# ASD2612.net
KiCad netlist of a schematic drawn in EAGLE
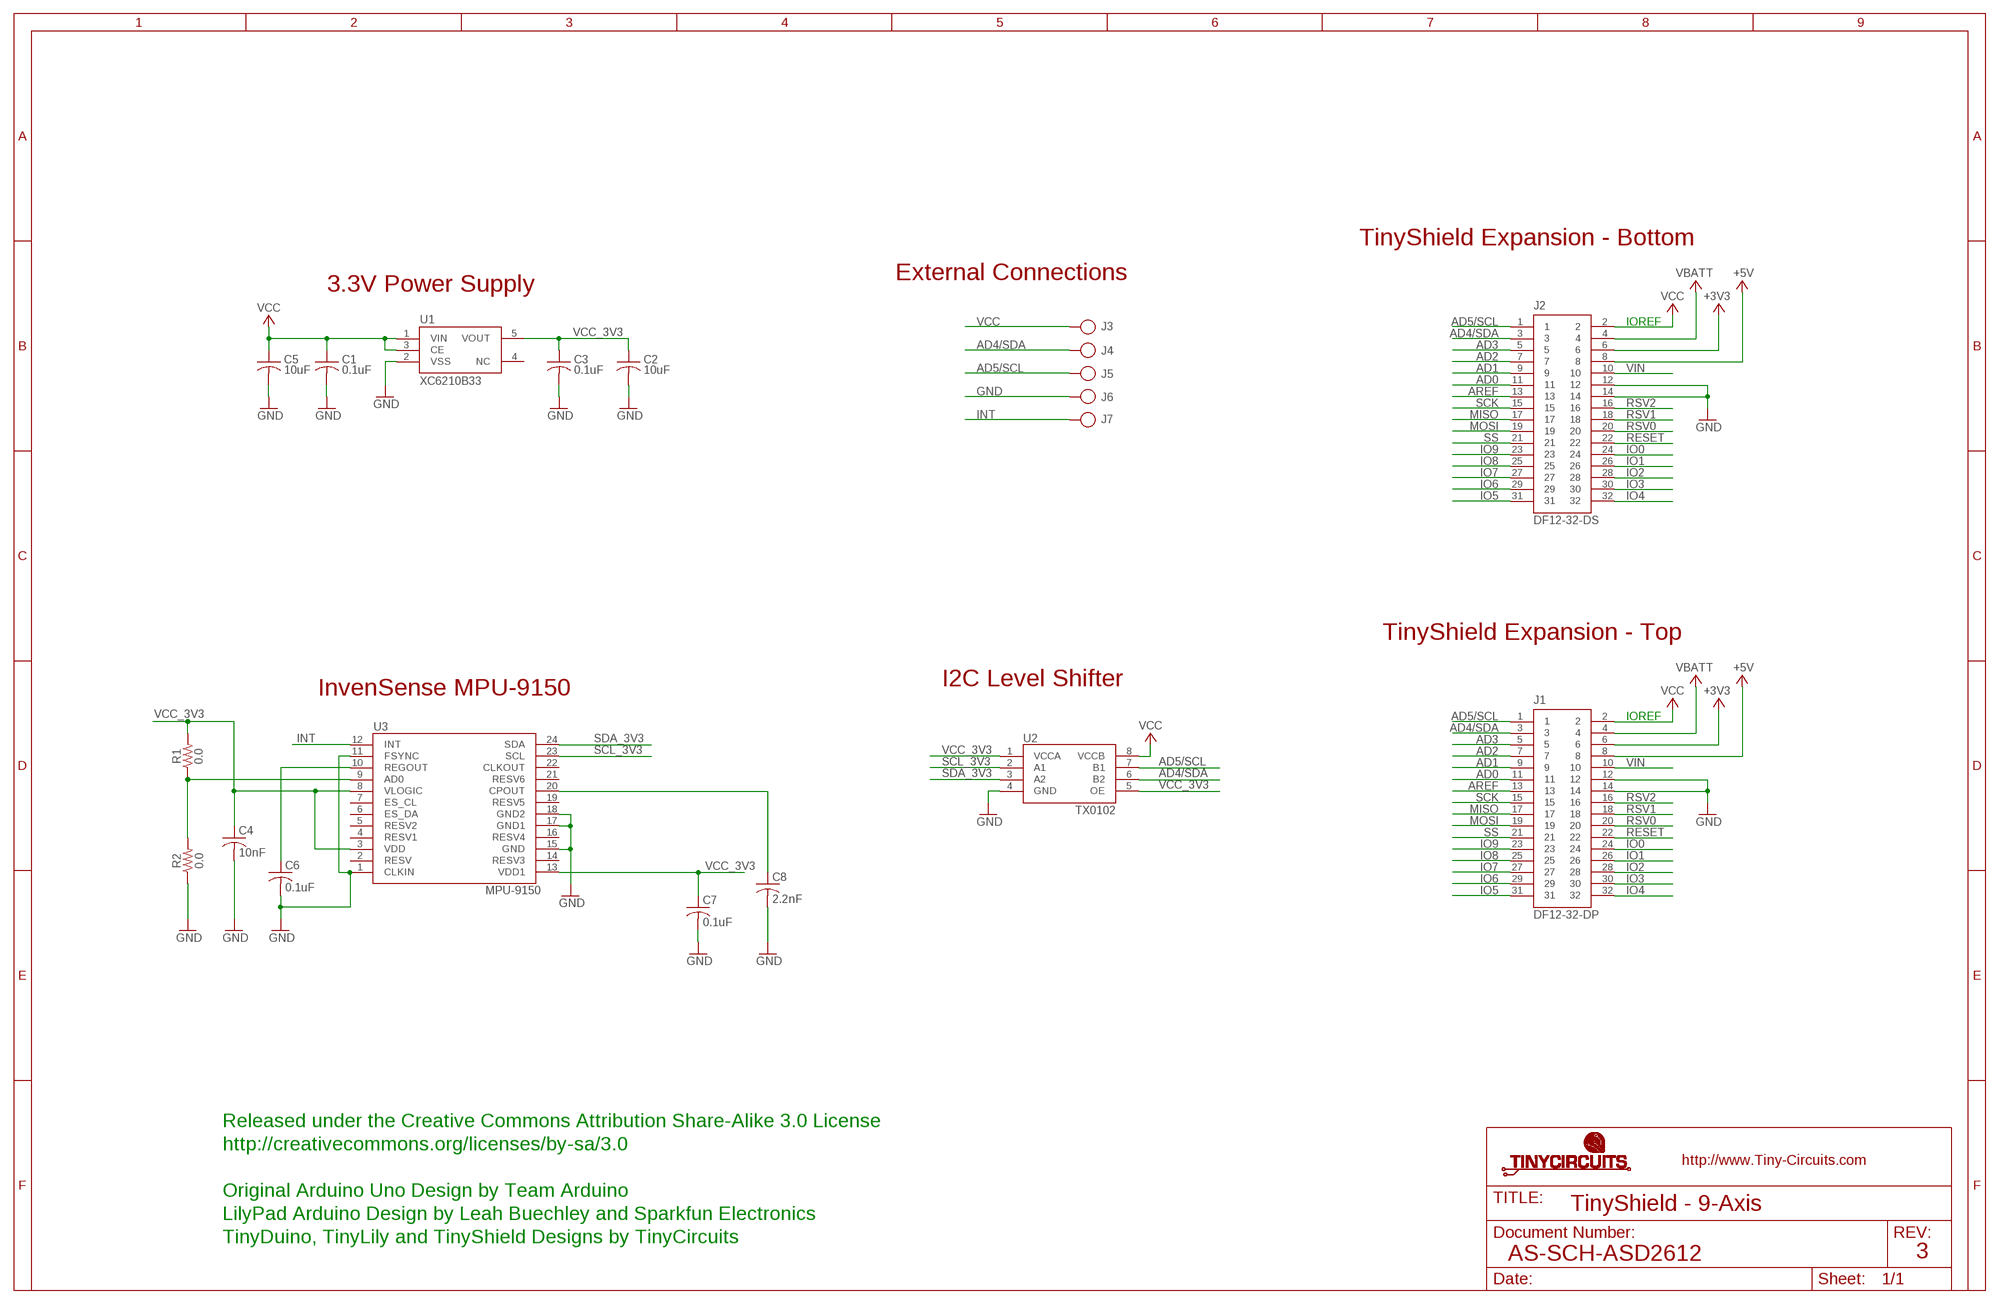
[diagram p0: schematic, sheet 1]

(export (version "E")
  (design (tool "Eeschema 10.0.6"))
  (components
    (comp (ref "C1")
      (value "0.1uF")
      (footprint "eagle-import:C0402")
      (fields (field (name "PARTNO") "AS-ITM-00008") (field (name "PARTNO_1") "AS-ITM-00008"))
      (libsource (lib "eagle-import") (part "AS-ITM-00008"))
    )
    (comp (ref "C2")
      (value "10uF")
      (footprint "eagle-import:C0805")
      (fields (field (name "PARTNO") "AS-ITM-00045") (field (name "PARTNO_1") "AS-ITM-00045"))
      (libsource (lib "eagle-import") (part "AS-ITM-00045"))
    )
    (comp (ref "C3")
      (value "0.1uF")
      (footprint "eagle-import:C0402")
      (fields (field (name "PARTNO") "AS-ITM-00008") (field (name "PARTNO_1") "AS-ITM-00008"))
      (libsource (lib "eagle-import") (part "AS-ITM-00008"))
    )
    (comp (ref "C4")
      (value "10nF")
      (footprint "eagle-import:C0402")
      (fields (field (name "PARTNO") "AS-ITM-00084"))
      (libsource (lib "eagle-import") (part "AS-ITM-00084"))
    )
    (comp (ref "C5")
      (value "10uF")
      (footprint "eagle-import:C0805")
      (fields (field (name "PARTNO") "AS-ITM-00045"))
      (libsource (lib "eagle-import") (part "AS-ITM-00045"))
    )
    (comp (ref "C6")
      (value "0.1uF")
      (footprint "eagle-import:C0402")
      (fields (field (name "PARTNO") "AS-ITM-00008"))
      (libsource (lib "eagle-import") (part "AS-ITM-00008"))
    )
    (comp (ref "C7")
      (value "0.1uF")
      (footprint "eagle-import:C0402")
      (fields (field (name "PARTNO") "AS-ITM-00008"))
      (libsource (lib "eagle-import") (part "AS-ITM-00008"))
    )
    (comp (ref "C8")
      (value "2.2nF")
      (footprint "eagle-import:C0402")
      (fields (field (name "PARTNO") "AS-ITM-00085"))
      (libsource (lib "eagle-import") (part "AS-ITM-00085"))
    )
    (comp (ref "J1")
      (value "DF12-32-DP")
      (footprint "eagle-import:DF12-32-DP")
      (fields (field (name "PARTNO") "AS-ITM-00015") (field (name "PARTNO_1") "AS-ITM-00015"))
      (libsource (lib "eagle-import") (part "AS-ITM-00015"))
    )
    (comp (ref "J2")
      (value "DF12-32-DS")
      (footprint "eagle-import:DF12-32-DS")
      (fields (field (name "PARTNO") "AS-ITM-00012") (field (name "PARTNO_1") "AS-ITM-00012"))
      (libsource (lib "eagle-import") (part "AS-ITM-00012"))
    )
    (comp (ref "J3")
      (value "PIN_1X.1\"")
      (footprint "eagle-import:1X.1_")
      (libsource (lib "eagle-import") (part "PIN_1X.1{dblquote}"))
    )
    (comp (ref "J4")
      (value "PIN_1X.1\"")
      (footprint "eagle-import:1X.1_")
      (libsource (lib "eagle-import") (part "PIN_1X.1{dblquote}"))
    )
    (comp (ref "J5")
      (value "PIN_1X.1\"")
      (footprint "eagle-import:1X.1_")
      (libsource (lib "eagle-import") (part "PIN_1X.1{dblquote}"))
    )
    (comp (ref "J6")
      (value "PIN_1X.1\"")
      (footprint "eagle-import:1X.1_")
      (libsource (lib "eagle-import") (part "PIN_1X.1{dblquote}"))
    )
    (comp (ref "J7")
      (value "PIN_1X.1\"")
      (footprint "eagle-import:1X.1_")
      (libsource (lib "eagle-import") (part "PIN_1X.1{dblquote}"))
    )
    (comp (ref "R1")
      (value "0.0")
      (footprint "eagle-import:0402")
      (fields (field (name "PARTNO") "AS-ITM-00076"))
      (libsource (lib "eagle-import") (part "AS-ITM-00076"))
    )
    (comp (ref "R2")
      (value "AS-ITM-000760402_SHORT")
      (footprint "eagle-import:0402_SHORT")
      (libsource (lib "eagle-import") (part "AS-ITM-000760402_SHORT"))
    )
    (comp (ref "U1")
      (value "XC6210B33")
      (footprint "eagle-import:SOT-25")
      (fields (field (name "PARTNO") "AS-ITM-00046"))
      (libsource (lib "eagle-import") (part "AS-ITM-00046"))
    )
    (comp (ref "U2")
      (value "TX0102")
      (footprint "eagle-import:DQE(R-PX2SON-N8)")
      (fields (field (name "PARTNO") "AS-ITM-00073"))
      (libsource (lib "eagle-import") (part "AS-ITM-00073"))
    )
    (comp (ref "U3")
      (value "MPU-9150")
      (footprint "eagle-import:MPU-9150")
      (fields (field (name "PARTNO") "AS-ITM-00081"))
      (libsource (lib "eagle-import") (part "AS-ITM-00081"))
    )
  )
  (nets
    (net (code "1") (name "+3V3") (class "Default")
      (node (ref "J1") (pin "6") (pinfunction "6_6") (pintype "bidirectional"))
      (node (ref "J2") (pin "6") (pinfunction "6_6") (pintype "bidirectional"))
    )
    (net (code "2") (name "+5V") (class "Default")
      (node (ref "J1") (pin "8") (pinfunction "8_8") (pintype "bidirectional"))
      (node (ref "J2") (pin "8") (pinfunction "8_8") (pintype "bidirectional"))
    )
    (net (code "3") (name "/AD0") (class "Default")
      (node (ref "J1") (pin "11") (pinfunction "11_11") (pintype "bidirectional"))
      (node (ref "J2") (pin "11") (pinfunction "11_11") (pintype "bidirectional"))
    )
    (net (code "4") (name "/AD1") (class "Default")
      (node (ref "J1") (pin "9") (pinfunction "9_9") (pintype "bidirectional"))
      (node (ref "J2") (pin "9") (pinfunction "9_9") (pintype "bidirectional"))
    )
    (net (code "5") (name "/AD2") (class "Default")
      (node (ref "J1") (pin "7") (pinfunction "7_7") (pintype "bidirectional"))
      (node (ref "J2") (pin "7") (pinfunction "7_7") (pintype "bidirectional"))
    )
    (net (code "6") (name "/AD3") (class "Default")
      (node (ref "J1") (pin "5") (pinfunction "5_5") (pintype "bidirectional"))
      (node (ref "J2") (pin "5") (pinfunction "5_5") (pintype "bidirectional"))
    )
    (net (code "7") (name "/AD4{slash}SDA") (class "Default")
      (node (ref "J1") (pin "3") (pinfunction "3_3") (pintype "bidirectional"))
      (node (ref "J2") (pin "3") (pinfunction "3_3") (pintype "bidirectional"))
      (node (ref "J4") (pin "1") (pinfunction "1_1") (pintype "bidirectional"))
      (node (ref "U2") (pin "6") (pinfunction "B2_6") (pintype "bidirectional"))
    )
    (net (code "8") (name "/AD5{slash}SCL") (class "Default")
      (node (ref "J1") (pin "1") (pinfunction "1_1") (pintype "bidirectional"))
      (node (ref "J2") (pin "1") (pinfunction "1_1") (pintype "bidirectional"))
      (node (ref "J5") (pin "1") (pinfunction "1_1") (pintype "bidirectional"))
      (node (ref "U2") (pin "7") (pinfunction "B1_7") (pintype "bidirectional"))
    )
    (net (code "9") (name "/AREF") (class "Default")
      (node (ref "J1") (pin "13") (pinfunction "13_13") (pintype "bidirectional"))
      (node (ref "J2") (pin "13") (pinfunction "13_13") (pintype "bidirectional"))
    )
    (net (code "10") (name "/INT") (class "Default")
      (node (ref "J7") (pin "1") (pinfunction "1_1") (pintype "bidirectional"))
      (node (ref "U3") (pin "12") (pinfunction "INT_12") (pintype "bidirectional"))
    )
    (net (code "11") (name "/IO0") (class "Default")
      (node (ref "J1") (pin "24") (pinfunction "24_24") (pintype "bidirectional"))
      (node (ref "J2") (pin "24") (pinfunction "24_24") (pintype "bidirectional"))
    )
    (net (code "12") (name "/IO1") (class "Default")
      (node (ref "J1") (pin "26") (pinfunction "26_26") (pintype "bidirectional"))
      (node (ref "J2") (pin "26") (pinfunction "26_26") (pintype "bidirectional"))
    )
    (net (code "13") (name "/IO2") (class "Default")
      (node (ref "J1") (pin "28") (pinfunction "28_28") (pintype "bidirectional"))
      (node (ref "J2") (pin "28") (pinfunction "28_28") (pintype "bidirectional"))
    )
    (net (code "14") (name "/IO3") (class "Default")
      (node (ref "J1") (pin "30") (pinfunction "30_30") (pintype "bidirectional"))
      (node (ref "J2") (pin "30") (pinfunction "30_30") (pintype "bidirectional"))
    )
    (net (code "15") (name "/IO4") (class "Default")
      (node (ref "J1") (pin "32") (pinfunction "32_32") (pintype "bidirectional"))
      (node (ref "J2") (pin "32") (pinfunction "32_32") (pintype "bidirectional"))
    )
    (net (code "16") (name "/IO5") (class "Default")
      (node (ref "J1") (pin "31") (pinfunction "31_31") (pintype "bidirectional"))
      (node (ref "J2") (pin "31") (pinfunction "31_31") (pintype "bidirectional"))
    )
    (net (code "17") (name "/IO6") (class "Default")
      (node (ref "J1") (pin "29") (pinfunction "29_29") (pintype "bidirectional"))
      (node (ref "J2") (pin "29") (pinfunction "29_29") (pintype "bidirectional"))
    )
    (net (code "18") (name "/IO7") (class "Default")
      (node (ref "J1") (pin "27") (pinfunction "27_27") (pintype "bidirectional"))
      (node (ref "J2") (pin "27") (pinfunction "27_27") (pintype "bidirectional"))
    )
    (net (code "19") (name "/IO8") (class "Default")
      (node (ref "J1") (pin "25") (pinfunction "25_25") (pintype "bidirectional"))
      (node (ref "J2") (pin "25") (pinfunction "25_25") (pintype "bidirectional"))
    )
    (net (code "20") (name "/IO9") (class "Default")
      (node (ref "J1") (pin "23") (pinfunction "23_23") (pintype "bidirectional"))
      (node (ref "J2") (pin "23") (pinfunction "23_23") (pintype "bidirectional"))
    )
    (net (code "21") (name "/MISO") (class "Default")
      (node (ref "J1") (pin "17") (pinfunction "17_17") (pintype "bidirectional"))
      (node (ref "J2") (pin "17") (pinfunction "17_17") (pintype "bidirectional"))
    )
    (net (code "22") (name "/MOSI") (class "Default")
      (node (ref "J1") (pin "19") (pinfunction "19_19") (pintype "bidirectional"))
      (node (ref "J2") (pin "19") (pinfunction "19_19") (pintype "bidirectional"))
    )
    (net (code "23") (name "/RESET") (class "Default")
      (node (ref "J1") (pin "22") (pinfunction "22_22") (pintype "bidirectional"))
      (node (ref "J2") (pin "22") (pinfunction "22_22") (pintype "bidirectional"))
    )
    (net (code "24") (name "/RSV0") (class "Default")
      (node (ref "J1") (pin "20") (pinfunction "20_20") (pintype "bidirectional"))
      (node (ref "J2") (pin "20") (pinfunction "20_20") (pintype "bidirectional"))
    )
    (net (code "25") (name "/RSV1") (class "Default")
      (node (ref "J1") (pin "18") (pinfunction "18_18") (pintype "bidirectional"))
      (node (ref "J2") (pin "18") (pinfunction "18_18") (pintype "bidirectional"))
    )
    (net (code "26") (name "/RSV2") (class "Default")
      (node (ref "J1") (pin "16") (pinfunction "16_16") (pintype "bidirectional"))
      (node (ref "J2") (pin "16") (pinfunction "16_16") (pintype "bidirectional"))
    )
    (net (code "27") (name "/SCK") (class "Default")
      (node (ref "J1") (pin "15") (pinfunction "15_15") (pintype "bidirectional"))
      (node (ref "J2") (pin "15") (pinfunction "15_15") (pintype "bidirectional"))
    )
    (net (code "28") (name "/SCL_3V3") (class "Default")
      (node (ref "U2") (pin "2") (pinfunction "A1_2") (pintype "bidirectional"))
      (node (ref "U3") (pin "23") (pinfunction "SCL_23") (pintype "bidirectional"))
    )
    (net (code "29") (name "/SDA_3V3") (class "Default")
      (node (ref "U2") (pin "3") (pinfunction "A2_3") (pintype "bidirectional"))
      (node (ref "U3") (pin "24") (pinfunction "SDA_24") (pintype "bidirectional"))
    )
    (net (code "30") (name "/SS") (class "Default")
      (node (ref "J1") (pin "21") (pinfunction "21_21") (pintype "bidirectional"))
      (node (ref "J2") (pin "21") (pinfunction "21_21") (pintype "bidirectional"))
    )
    (net (code "31") (name "/VCC_3V3") (class "Default")
      (node (ref "C2") (pin "1") (pinfunction "1_1") (pintype "passive"))
      (node (ref "C3") (pin "1") (pinfunction "1_1") (pintype "passive"))
      (node (ref "C4") (pin "1") (pinfunction "1_1") (pintype "passive"))
      (node (ref "C7") (pin "1") (pinfunction "1_1") (pintype "passive"))
      (node (ref "R1") (pin "2") (pinfunction "2_2") (pintype "passive"))
      (node (ref "U1") (pin "5") (pinfunction "VOUT_5") (pintype "bidirectional"))
      (node (ref "U2") (pin "1") (pinfunction "VCCA_1") (pintype "bidirectional"))
      (node (ref "U2") (pin "5") (pinfunction "OE_5") (pintype "bidirectional"))
      (node (ref "U3") (pin "13") (pinfunction "VDD1_13") (pintype "bidirectional"))
      (node (ref "U3") (pin "3") (pinfunction "VDD_3") (pintype "bidirectional"))
      (node (ref "U3") (pin "8") (pinfunction "VLOGIC_8") (pintype "bidirectional"))
    )
    (net (code "32") (name "/VIN") (class "Default")
      (node (ref "J1") (pin "10") (pinfunction "10_10") (pintype "bidirectional"))
      (node (ref "J2") (pin "10") (pinfunction "10_10") (pintype "bidirectional"))
    )
    (net (code "33") (name "GND") (class "Default")
      (node (ref "C1") (pin "2") (pinfunction "2_2") (pintype "passive"))
      (node (ref "C2") (pin "2") (pinfunction "2_2") (pintype "passive"))
      (node (ref "C3") (pin "2") (pinfunction "2_2") (pintype "passive"))
      (node (ref "C4") (pin "2") (pinfunction "2_2") (pintype "passive"))
      (node (ref "C5") (pin "2") (pinfunction "2_2") (pintype "passive"))
      (node (ref "C6") (pin "2") (pinfunction "2_2") (pintype "passive"))
      (node (ref "C7") (pin "2") (pinfunction "2_2") (pintype "passive"))
      (node (ref "C8") (pin "2") (pinfunction "2_2") (pintype "passive"))
      (node (ref "J1") (pin "12") (pinfunction "12_12") (pintype "bidirectional"))
      (node (ref "J1") (pin "14") (pinfunction "14_14") (pintype "bidirectional"))
      (node (ref "J2") (pin "12") (pinfunction "12_12") (pintype "bidirectional"))
      (node (ref "J2") (pin "14") (pinfunction "14_14") (pintype "bidirectional"))
      (node (ref "J6") (pin "1") (pinfunction "1_1") (pintype "bidirectional"))
      (node (ref "R2") (pin "1") (pinfunction "1_1") (pintype "passive"))
      (node (ref "U1") (pin "2") (pinfunction "VSS_2") (pintype "power_in"))
      (node (ref "U2") (pin "4") (pinfunction "GND_4") (pintype "bidirectional"))
      (node (ref "U3") (pin "1") (pinfunction "CLKIN_1") (pintype "bidirectional"))
      (node (ref "U3") (pin "11") (pinfunction "FSYNC_11") (pintype "bidirectional"))
      (node (ref "U3") (pin "15") (pinfunction "GND_15") (pintype "bidirectional"))
      (node (ref "U3") (pin "17") (pinfunction "GND1_17") (pintype "bidirectional"))
      (node (ref "U3") (pin "18") (pinfunction "GND2_18") (pintype "bidirectional"))
    )
    (net (code "34") (name "Net-(U3-AD0)") (class "Default")
      (node (ref "R1") (pin "1") (pinfunction "1_1") (pintype "passive"))
      (node (ref "R2") (pin "2") (pinfunction "2_2") (pintype "passive"))
      (node (ref "U3") (pin "9") (pinfunction "AD0_9") (pintype "bidirectional"))
    )
    (net (code "35") (name "Net-(U3-CPOUT)") (class "Default")
      (node (ref "C8") (pin "1") (pinfunction "1_1") (pintype "passive"))
      (node (ref "U3") (pin "20") (pinfunction "CPOUT_20") (pintype "bidirectional"))
    )
    (net (code "36") (name "Net-(U3-REGOUT)") (class "Default")
      (node (ref "C6") (pin "1") (pinfunction "1_1") (pintype "passive"))
      (node (ref "U3") (pin "10") (pinfunction "REGOUT_10") (pintype "bidirectional"))
    )
    (net (code "37") (name "VBATT") (class "Default")
      (node (ref "J1") (pin "4") (pinfunction "4_4") (pintype "bidirectional"))
      (node (ref "J2") (pin "4") (pinfunction "4_4") (pintype "bidirectional"))
    )
    (net (code "38") (name "VCC") (class "Default")
      (node (ref "C1") (pin "1") (pinfunction "1_1") (pintype "passive"))
      (node (ref "C5") (pin "1") (pinfunction "1_1") (pintype "passive"))
      (node (ref "J1") (pin "2") (pinfunction "2_2") (pintype "bidirectional"))
      (node (ref "J2") (pin "2") (pinfunction "2_2") (pintype "bidirectional"))
      (node (ref "J3") (pin "1") (pinfunction "1_1") (pintype "bidirectional"))
      (node (ref "U1") (pin "1") (pinfunction "VIN_1") (pintype "bidirectional"))
      (node (ref "U1") (pin "3") (pinfunction "CE_3") (pintype "bidirectional"))
      (node (ref "U2") (pin "8") (pinfunction "VCCB_8") (pintype "bidirectional"))
    )
    (net (code "39") (name "unconnected-(U1-NC-Pad4)") (class "Default")
      (node (ref "U1") (pin "4") (pinfunction "NC_4") (pintype "bidirectional"))
    )
    (net (code "40") (name "unconnected-(U3-CLKOUT-Pad22)") (class "Default")
      (node (ref "U3") (pin "22") (pinfunction "CLKOUT_22") (pintype "bidirectional"))
    )
    (net (code "41") (name "unconnected-(U3-ES_CL-Pad7)") (class "Default")
      (node (ref "U3") (pin "7") (pinfunction "ES_CL_7") (pintype "bidirectional"))
    )
    (net (code "42") (name "unconnected-(U3-ES_DA-Pad6)") (class "Default")
      (node (ref "U3") (pin "6") (pinfunction "ES_DA_6") (pintype "bidirectional"))
    )
    (net (code "43") (name "unconnected-(U3-RESV-Pad2)") (class "Default")
      (node (ref "U3") (pin "2") (pinfunction "RESV_2") (pintype "bidirectional"))
    )
    (net (code "44") (name "unconnected-(U3-RESV1-Pad4)") (class "Default")
      (node (ref "U3") (pin "4") (pinfunction "RESV1_4") (pintype "bidirectional"))
    )
    (net (code "45") (name "unconnected-(U3-RESV2-Pad5)") (class "Default")
      (node (ref "U3") (pin "5") (pinfunction "RESV2_5") (pintype "bidirectional"))
    )
    (net (code "46") (name "unconnected-(U3-RESV3-Pad14)") (class "Default")
      (node (ref "U3") (pin "14") (pinfunction "RESV3_14") (pintype "bidirectional"))
    )
    (net (code "47") (name "unconnected-(U3-RESV4-Pad16)") (class "Default")
      (node (ref "U3") (pin "16") (pinfunction "RESV4_16") (pintype "bidirectional"))
    )
    (net (code "48") (name "unconnected-(U3-RESV5-Pad19)") (class "Default")
      (node (ref "U3") (pin "19") (pinfunction "RESV5_19") (pintype "bidirectional"))
    )
    (net (code "49") (name "unconnected-(U3-RESV6-Pad21)") (class "Default")
      (node (ref "U3") (pin "21") (pinfunction "RESV6_21") (pintype "bidirectional"))
    )
  )
)
